# Regulators.net
KiCad netlist of a schematic drawn in Altium Designer
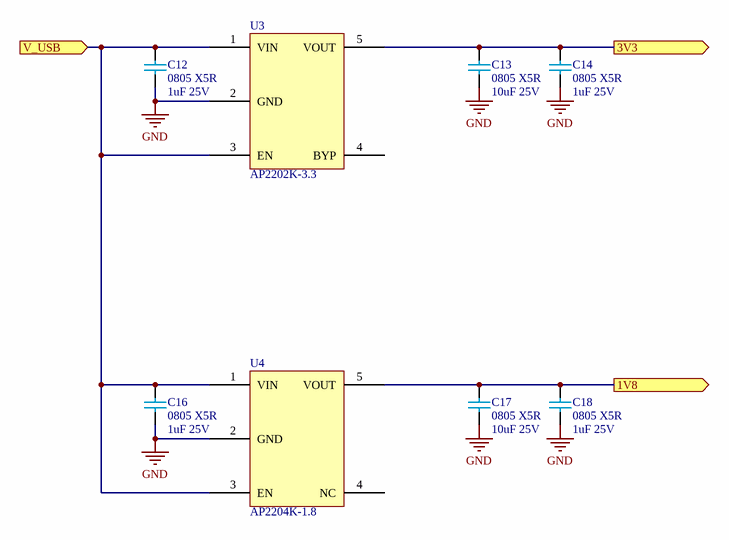
[diagram p0: Regulators.SchDoc]

(export (version "E")
  (design (tool "Eeschema 10.0.6"))
  (components
    (comp (ref "C12")
      (value "0805 X5R")
      (footprint "0805 - TALL")
      (description "0805, X5R or better")
      (fields (field (name "ALTIUM_VALUE") "1uF 25V"))
      (libsource (lib "Chip_Passives") (part "Cap 1uF 25V"))
    )
    (comp (ref "C13")
      (value "0805 X5R")
      (footprint "0805 - TALL")
      (description "0805, X5R or better")
      (fields (field (name "ALTIUM_VALUE") "10uF 25V"))
      (libsource (lib "Chip_Passives") (part "Cap 10uF 25V"))
    )
    (comp (ref "C14")
      (value "0805 X5R")
      (footprint "0805 - TALL")
      (description "0805, X5R or better")
      (fields (field (name "ALTIUM_VALUE") "1uF 25V"))
      (libsource (lib "Chip_Passives") (part "Cap 1uF 25V"))
    )
    (comp (ref "C16")
      (value "0805 X5R")
      (footprint "0805 - TALL")
      (description "0805, X5R or better")
      (fields (field (name "ALTIUM_VALUE") "1uF 25V"))
      (libsource (lib "Chip_Passives") (part "Cap 1uF 25V"))
    )
    (comp (ref "C17")
      (value "0805 X5R")
      (footprint "0805 - TALL")
      (description "0805, X5R or better")
      (fields (field (name "ALTIUM_VALUE") "10uF 25V"))
      (libsource (lib "Chip_Passives") (part "Cap 10uF 25V"))
    )
    (comp (ref "C18")
      (value "0805 X5R")
      (footprint "0805 - TALL")
      (description "0805, X5R or better")
      (fields (field (name "ALTIUM_VALUE") "1uF 25V"))
      (libsource (lib "Chip_Passives") (part "Cap 1uF 25V"))
    )
    (comp (ref "U3")
      (value "AP2202K-3.3")
      (footprint "AP2202 - SOT95P270X145-5N")
      (description "3.3V 150mA LDO regulator")
      (libsource (lib "PowerSupply") (part "AP2202K-3.3"))
    )
    (comp (ref "U4")
      (value "AP2204K-1.8")
      (footprint "AP2202 - SOT95P270X145-5N")
      (description "Linear Voltage Regulator IC 1 Output 150mA SOT-23-5")
      (libsource (lib "PowerSupply") (part "AP2204K-1.8"))
    )
  )
  (nets
    (net (code "1") (name "/1V8") (class "Default")
      (node (ref "C17") (pin "2") (pinfunction "2_2") (pintype "passive"))
      (node (ref "C18") (pin "2") (pinfunction "2_2") (pintype "passive"))
      (node (ref "U4") (pin "5") (pinfunction "VOUT_5") (pintype "passive"))
    )
    (net (code "2") (name "/3V3") (class "Default")
      (node (ref "C13") (pin "2") (pinfunction "2_2") (pintype "passive"))
      (node (ref "C14") (pin "2") (pinfunction "2_2") (pintype "passive"))
      (node (ref "U3") (pin "5") (pinfunction "VOUT_5") (pintype "passive"))
    )
    (net (code "3") (name "/V_USB") (class "Default")
      (node (ref "C12") (pin "2") (pinfunction "2_2") (pintype "passive"))
      (node (ref "C16") (pin "2") (pinfunction "2_2") (pintype "passive"))
      (node (ref "U3") (pin "1") (pinfunction "VIN_1") (pintype "passive"))
      (node (ref "U3") (pin "3") (pinfunction "EN_3") (pintype "passive"))
      (node (ref "U4") (pin "1") (pinfunction "VIN_1") (pintype "passive"))
      (node (ref "U4") (pin "3") (pinfunction "EN_3") (pintype "passive"))
    )
    (net (code "4") (name "GND") (class "Default")
      (node (ref "C12") (pin "1") (pinfunction "1_1") (pintype "passive"))
      (node (ref "C13") (pin "1") (pinfunction "1_1") (pintype "passive"))
      (node (ref "C14") (pin "1") (pinfunction "1_1") (pintype "passive"))
      (node (ref "C16") (pin "1") (pinfunction "1_1") (pintype "passive"))
      (node (ref "C17") (pin "1") (pinfunction "1_1") (pintype "passive"))
      (node (ref "C18") (pin "1") (pinfunction "1_1") (pintype "passive"))
      (node (ref "U3") (pin "2") (pinfunction "GND_2") (pintype "passive"))
      (node (ref "U4") (pin "2") (pinfunction "GND_2") (pintype "passive"))
    )
    (net (code "5") (name "unconnected-(U3-BYP-Pad4)") (class "Default")
      (node (ref "U3") (pin "4") (pinfunction "BYP_4") (pintype "passive"))
    )
    (net (code "6") (name "unconnected-(U4-NC-Pad4)") (class "Default")
      (node (ref "U4") (pin "4") (pinfunction "NC_4") (pintype "passive"))
    )
  )
)
